# Schematic.net
KiCad netlist of a schematic drawn in Altium Designer
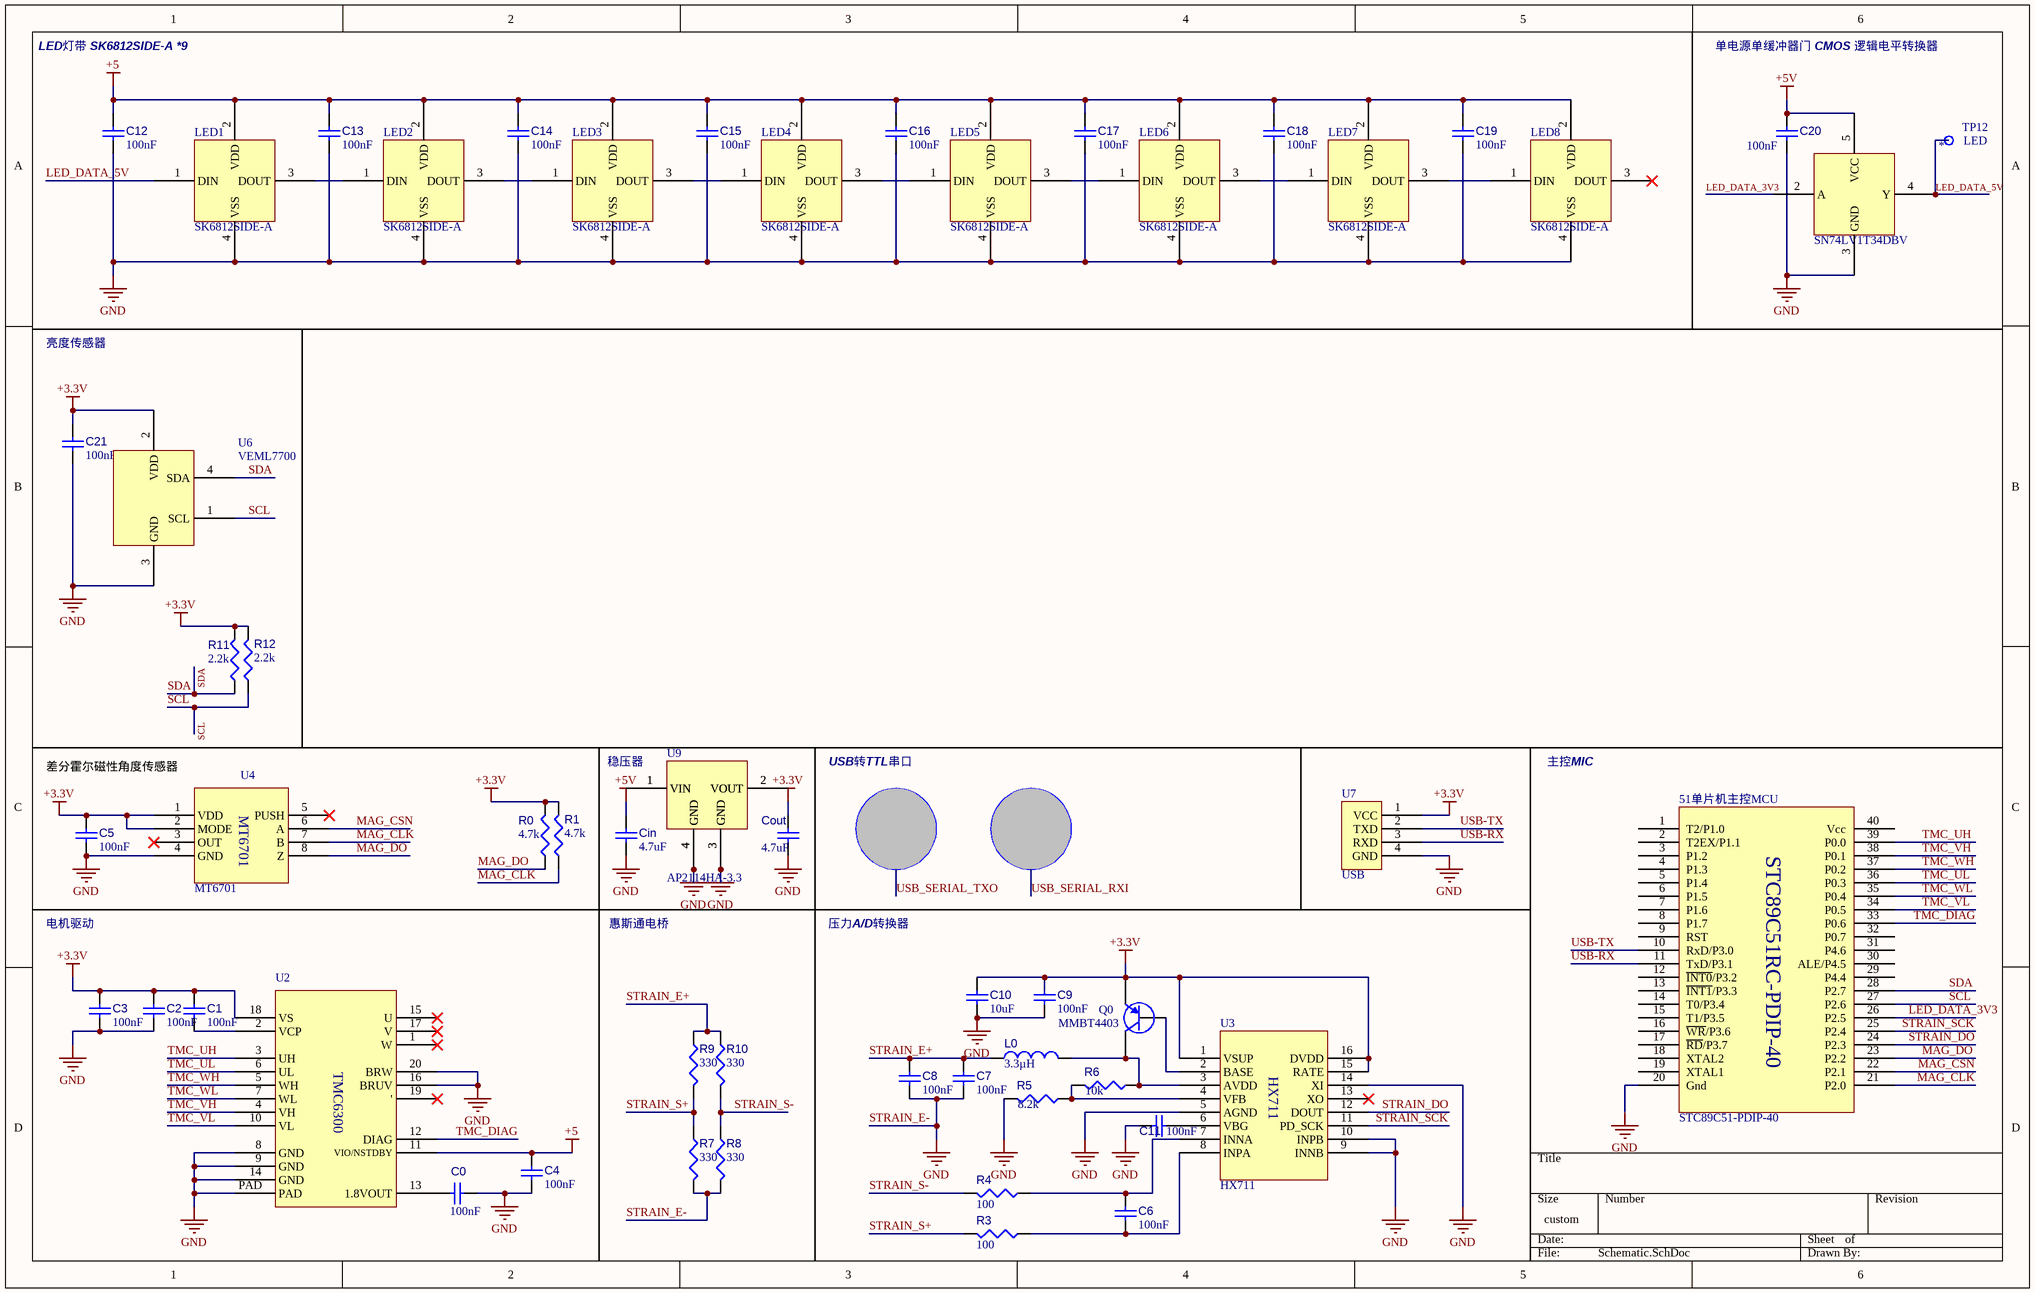
[diagram p0: Schematic.SchDoc]

(export (version "E")
  (design (tool "Eeschema 10.0.6"))
  (components
    (comp (ref "*")
      (value "SN74LV1T34DBV")
      (footprint "封装.SN74LV1T34DBVR")
      (description "电流放大器")
      (libsource (lib "DigiPCBA Workspace") (part "SN74LV1T34DBV"))
    )
    (comp (ref "51单片机主控MCU")
      (value "STC89C51-PDIP-40")
      (footprint "封装.STC89C51-PDIP-40")
      (description "主控MCU")
      (libsource (lib "DigiPCBA Workspace") (part "STC89C51-PDIP-40"))
    )
    (comp (ref "C0")
      (value "100nF")
      (footprint "CAPC1005X56X25LL10T15")
      (description "Chip Capacitor, 0.1 uF, +/- 5%, 16 V, 0402 (1005 Metric)")
      (fields (field (name "TOLERANCE") "5%") (field (name "Comment") "Capacitor 0.1 uF +/- 5% 16 V 0402"))
      (libsource (lib "IC") (part "CAP-NP-2"))
    )
    (comp (ref "C1")
      (value "100nF")
      (footprint "CAPC1005X56X25LL10T15")
      (description "Chip Capacitor, 0.1 uF, +/- 5%, 16 V, 0402 (1005 Metric)")
      (fields (field (name "TOLERANCE") "5%") (field (name "Comment") "Capacitor 0.1 uF +/- 5% 16 V 0402"))
      (libsource (lib "IC") (part "CAP-NP-2"))
    )
    (comp (ref "C2")
      (value "100nF")
      (footprint "CAPC1005X56X25LL10T15")
      (description "Chip Capacitor, 0.1 uF, +/- 5%, 16 V, 0402 (1005 Metric)")
      (fields (field (name "TOLERANCE") "5%") (field (name "Comment") "Capacitor 0.1 uF +/- 5% 16 V 0402"))
      (libsource (lib "IC") (part "CAP-NP-2"))
    )
    (comp (ref "C3")
      (value "100nF")
      (footprint "CAPC1005X56X25LL10T15")
      (description "Chip Capacitor, 0.1 uF, +/- 5%, 16 V, 0402 (1005 Metric)")
      (fields (field (name "TOLERANCE") "5%") (field (name "Comment") "Capacitor 0.1 uF +/- 5% 16 V 0402"))
      (libsource (lib "IC") (part "CAP-NP-2"))
    )
    (comp (ref "C4")
      (value "100nF")
      (footprint "CAPC1005X56X25LL10T15")
      (description "Chip Capacitor, 0.1 uF, +/- 5%, 16 V, 0402 (1005 Metric)")
      (fields (field (name "TOLERANCE") "5%") (field (name "Comment") "Capacitor 0.1 uF +/- 5% 16 V 0402"))
      (libsource (lib "IC") (part "CAP-NP-2"))
    )
    (comp (ref "C5")
      (value "100nF")
      (footprint "CAPC1005X56X25LL10T15")
      (description "Chip Capacitor, 0.1 uF, +/- 5%, 16 V, 0402 (1005 Metric)")
      (fields (field (name "TOLERANCE") "5%") (field (name "Comment") "Capacitor 0.1 uF +/- 5% 16 V 0402"))
      (libsource (lib "IC") (part "CAP-NP-2"))
    )
    (comp (ref "C6")
      (value "100nF")
      (footprint "CAPC1005X56X25LL10T15")
      (description "Chip Capacitor, 0.1 uF, +/- 5%, 16 V, 0402 (1005 Metric)")
      (fields (field (name "TOLERANCE") "5%") (field (name "Comment") "Capacitor 0.1 uF +/- 5% 16 V 0402"))
      (libsource (lib "IC") (part "CAP-NP-2"))
    )
    (comp (ref "C7")
      (value "100nF")
      (footprint "CAPC1005X56X25LL10T15")
      (description "Chip Capacitor, 0.1 uF, +/- 5%, 16 V, 0402 (1005 Metric)")
      (fields (field (name "TOLERANCE") "5%") (field (name "Comment") "Capacitor 0.1 uF +/- 5% 16 V 0402"))
      (libsource (lib "IC") (part "CAP-NP-2"))
    )
    (comp (ref "C8")
      (value "100nF")
      (footprint "CAPC1005X56X25LL10T15")
      (description "Chip Capacitor, 0.1 uF, +/- 5%, 16 V, 0402 (1005 Metric)")
      (fields (field (name "TOLERANCE") "5%") (field (name "Comment") "Capacitor 0.1 uF +/- 5% 16 V 0402"))
      (libsource (lib "IC") (part "CAP-NP-2"))
    )
    (comp (ref "C9")
      (value "100nF")
      (footprint "CAPC1005X56X25LL10T15")
      (description "Chip Capacitor, 0.1 uF, +/- 5%, 16 V, 0402 (1005 Metric)")
      (fields (field (name "TOLERANCE") "5%") (field (name "Comment") "Capacitor 0.1 uF +/- 5% 16 V 0402"))
      (libsource (lib "IC") (part "CAP-NP-2"))
    )
    (comp (ref "C10")
      (value "10uF")
      (footprint "CAPC1005X56X25LL10T15")
      (description "Chip Capacitor, 0.1 uF, +/- 5%, 16 V, 0402 (1005 Metric)")
      (fields (field (name "TOLERANCE") "5%") (field (name "Comment") "Capacitor 0.1 uF +/- 5% 16 V 0402"))
      (libsource (lib "IC") (part "CAP-NP-2"))
    )
    (comp (ref "C11")
      (value "100nF")
      (footprint "CAPC1005X56X25LL10T15")
      (description "Chip Capacitor, 0.1 uF, +/- 5%, 16 V, 0402 (1005 Metric)")
      (fields (field (name "TOLERANCE") "5%") (field (name "Comment") "Capacitor 0.1 uF +/- 5% 16 V 0402"))
      (libsource (lib "IC") (part "CAP-NP-2"))
    )
    (comp (ref "C12")
      (value "100nF")
      (footprint "CAPC1005X56X25LL10T15")
      (description "Chip Capacitor, 0.1 uF, +/- 5%, 16 V, 0402 (1005 Metric)")
      (fields (field (name "TOLERANCE") "5%") (field (name "Comment") "Capacitor 0.1 uF +/- 5% 16 V 0402"))
      (libsource (lib "IC") (part "CAP-NP-2"))
    )
    (comp (ref "C13")
      (value "100nF")
      (footprint "CAPC1005X56X25LL10T15")
      (description "Chip Capacitor, 0.1 uF, +/- 5%, 16 V, 0402 (1005 Metric)")
      (fields (field (name "TOLERANCE") "5%") (field (name "Comment") "Capacitor 0.1 uF +/- 5% 16 V 0402"))
      (libsource (lib "IC") (part "CAP-NP-2"))
    )
    (comp (ref "C14")
      (value "100nF")
      (footprint "CAPC1005X56X25LL10T15")
      (description "Chip Capacitor, 0.1 uF, +/- 5%, 16 V, 0402 (1005 Metric)")
      (fields (field (name "TOLERANCE") "5%") (field (name "Comment") "Capacitor 0.1 uF +/- 5% 16 V 0402"))
      (libsource (lib "IC") (part "CAP-NP-2"))
    )
    (comp (ref "C15")
      (value "100nF")
      (footprint "CAPC1005X56X25LL10T15")
      (description "Chip Capacitor, 0.1 uF, +/- 5%, 16 V, 0402 (1005 Metric)")
      (fields (field (name "TOLERANCE") "5%") (field (name "Comment") "Capacitor 0.1 uF +/- 5% 16 V 0402"))
      (libsource (lib "IC") (part "CAP-NP-2"))
    )
    (comp (ref "C16")
      (value "100nF")
      (footprint "CAPC1005X56X25LL10T15")
      (description "Chip Capacitor, 0.1 uF, +/- 5%, 16 V, 0402 (1005 Metric)")
      (fields (field (name "TOLERANCE") "5%") (field (name "Comment") "Capacitor 0.1 uF +/- 5% 16 V 0402"))
      (libsource (lib "IC") (part "CAP-NP-2"))
    )
    (comp (ref "C17")
      (value "100nF")
      (footprint "CAPC1005X56X25LL10T15")
      (description "Chip Capacitor, 0.1 uF, +/- 5%, 16 V, 0402 (1005 Metric)")
      (fields (field (name "TOLERANCE") "5%") (field (name "Comment") "Capacitor 0.1 uF +/- 5% 16 V 0402"))
      (libsource (lib "IC") (part "CAP-NP-2"))
    )
    (comp (ref "C18")
      (value "100nF")
      (footprint "CAPC1005X56X25LL10T15")
      (description "Chip Capacitor, 0.1 uF, +/- 5%, 16 V, 0402 (1005 Metric)")
      (fields (field (name "TOLERANCE") "5%") (field (name "Comment") "Capacitor 0.1 uF +/- 5% 16 V 0402"))
      (libsource (lib "IC") (part "CAP-NP-2"))
    )
    (comp (ref "C19")
      (value "100nF")
      (footprint "CAPC1005X56X25LL10T15")
      (description "Chip Capacitor, 0.1 uF, +/- 5%, 16 V, 0402 (1005 Metric)")
      (fields (field (name "TOLERANCE") "5%") (field (name "Comment") "Capacitor 0.1 uF +/- 5% 16 V 0402"))
      (libsource (lib "IC") (part "CAP-NP-2"))
    )
    (comp (ref "C20")
      (value "100nF")
      (footprint "CAPC1005X56X25LL10T15")
      (description "Chip Capacitor, 0.1 uF, +/- 5%, 16 V, 0402 (1005 Metric)")
      (fields (field (name "TOLERANCE") "5%") (field (name "Comment") "Capacitor 0.1 uF +/- 5% 16 V 0402"))
      (libsource (lib "IC") (part "CAP-NP-2"))
    )
    (comp (ref "C21")
      (value "100nF")
      (footprint "CAPC1005X56X25LL10T15")
      (description "Chip Capacitor, 0.1 uF, +/- 5%, 16 V, 0402 (1005 Metric)")
      (fields (field (name "TOLERANCE") "5%") (field (name "Comment") "Capacitor 0.1 uF +/- 5% 16 V 0402"))
      (libsource (lib "IC") (part "CAP-NP-2"))
    )
    (comp (ref "Cin")
      (value "4.7uF")
      (footprint "CAPC1005X56X25LL10T15")
      (description "Chip Capacitor, 0.1 uF, +/- 5%, 16 V, 0402 (1005 Metric)")
      (fields (field (name "TOLERANCE") "5%") (field (name "Comment") "Capacitor 0.1 uF +/- 5% 16 V 0402"))
      (libsource (lib "IC") (part "CAP-NP-2"))
    )
    (comp (ref "Cout")
      (value "4.7uF")
      (footprint "CAPC1005X56X25LL10T15")
      (description "Chip Capacitor, 0.1 uF, +/- 5%, 16 V, 0402 (1005 Metric)")
      (fields (field (name "TOLERANCE") "5%") (field (name "Comment") "Capacitor 0.1 uF +/- 5% 16 V 0402"))
      (libsource (lib "IC") (part "CAP-NP-2"))
    )
    (comp (ref "L0")
      (value "3.3µH")
      (footprint "INDC2520X120X60NL20T20")
      (description "Chip Inductor, 1 uH, +/- 20%, 1 MHz, -55 to 125 degC, 1008 (2520 Metric), RoHS, Tape and Reel")
      (fields (field (name "TOLERANCE") "20%") (field (name "MANUFACTURER") "Murata"))
      (libsource (lib "DigiPCBA Workspace") (part "IND-2"))
    )
    (comp (ref "LED1") (value "SK6812SIDE-A") (libsource (lib "DigiPCBA Workspace") (part "SK6812SIDE-A")))
    (comp (ref "LED2") (value "SK6812SIDE-A") (libsource (lib "DigiPCBA Workspace") (part "SK6812SIDE-A")))
    (comp (ref "LED3") (value "SK6812SIDE-A") (libsource (lib "DigiPCBA Workspace") (part "SK6812SIDE-A")))
    (comp (ref "LED4") (value "SK6812SIDE-A") (libsource (lib "DigiPCBA Workspace") (part "SK6812SIDE-A")))
    (comp (ref "LED5") (value "SK6812SIDE-A") (libsource (lib "DigiPCBA Workspace") (part "SK6812SIDE-A")))
    (comp (ref "LED6") (value "SK6812SIDE-A") (libsource (lib "DigiPCBA Workspace") (part "SK6812SIDE-A")))
    (comp (ref "LED7") (value "SK6812SIDE-A") (libsource (lib "DigiPCBA Workspace") (part "SK6812SIDE-A")))
    (comp (ref "LED8") (value "SK6812SIDE-A") (libsource (lib "DigiPCBA Workspace") (part "SK6812SIDE-A")))
    (comp (ref "Q0")
      (value "MMBT4403")
      (footprint "UNIC-TO-92-3")
      (description "Low Voltage High Current Small Signal PNP Transistor, 20 V, 700 mA, 3-Pin TO-92, RoHS")
      (fields (field (name "MANUFACTURER") "Unisonic"))
      (libsource (lib "DigiPCBA Workspace") (part "BJT-PNP-EBC-3"))
    )
    (comp (ref "R0")
      (value "4.7k")
      (footprint "RESC0402(1005)_L")
      (description "4K7 0.063W 1% 0402 (1005 Metric)  SMD")
      (fields (field (name "TOLERANCE") "1%") (field (name "POWER") "63mW"))
      (libsource (lib "DigiPCBA Workspace") (part "4D7KR2F"))
    )
    (comp (ref "R1")
      (value "4.7k")
      (footprint "RESC0402(1005)_L")
      (description "4K7 0.063W 1% 0402 (1005 Metric)  SMD")
      (fields (field (name "TOLERANCE") "1%") (field (name "POWER") "63mW"))
      (libsource (lib "DigiPCBA Workspace") (part "4D7KR2F"))
    )
    (comp (ref "R3")
      (value "100")
      (footprint "RESC0402(1005)_L")
      (description "4K7 0.063W 1% 0402 (1005 Metric)  SMD")
      (fields (field (name "TOLERANCE") "1%") (field (name "POWER") "63mW"))
      (libsource (lib "DigiPCBA Workspace") (part "4D7KR2F"))
    )
    (comp (ref "R4")
      (value "100")
      (footprint "RESC0402(1005)_L")
      (description "4K7 0.063W 1% 0402 (1005 Metric)  SMD")
      (fields (field (name "TOLERANCE") "1%") (field (name "POWER") "63mW"))
      (libsource (lib "DigiPCBA Workspace") (part "4D7KR2F"))
    )
    (comp (ref "R5")
      (value "8.2k")
      (footprint "RESC0402(1005)_L")
      (description "4K7 0.063W 1% 0402 (1005 Metric)  SMD")
      (fields (field (name "TOLERANCE") "1%") (field (name "POWER") "63mW"))
      (libsource (lib "DigiPCBA Workspace") (part "4D7KR2F"))
    )
    (comp (ref "R6")
      (value "10k")
      (footprint "RESC0402(1005)_L")
      (description "4K7 0.063W 1% 0402 (1005 Metric)  SMD")
      (fields (field (name "TOLERANCE") "1%") (field (name "POWER") "63mW"))
      (libsource (lib "DigiPCBA Workspace") (part "4D7KR2F"))
    )
    (comp (ref "R7")
      (value "330")
      (footprint "RESC0402(1005)_L")
      (description "4K7 0.063W 1% 0402 (1005 Metric)  SMD")
      (fields (field (name "TOLERANCE") "1%") (field (name "POWER") "63mW"))
      (libsource (lib "DigiPCBA Workspace") (part "4D7KR2F"))
    )
    (comp (ref "R8")
      (value "330")
      (footprint "RESC0402(1005)_L")
      (description "4K7 0.063W 1% 0402 (1005 Metric)  SMD")
      (fields (field (name "TOLERANCE") "1%") (field (name "POWER") "63mW"))
      (libsource (lib "DigiPCBA Workspace") (part "4D7KR2F"))
    )
    (comp (ref "R9")
      (value "330")
      (footprint "RESC0402(1005)_L")
      (description "4K7 0.063W 1% 0402 (1005 Metric)  SMD")
      (fields (field (name "TOLERANCE") "1%") (field (name "POWER") "63mW"))
      (libsource (lib "DigiPCBA Workspace") (part "4D7KR2F"))
    )
    (comp (ref "R10")
      (value "330")
      (footprint "RESC0402(1005)_L")
      (description "4K7 0.063W 1% 0402 (1005 Metric)  SMD")
      (fields (field (name "TOLERANCE") "1%") (field (name "POWER") "63mW"))
      (libsource (lib "DigiPCBA Workspace") (part "4D7KR2F"))
    )
    (comp (ref "R11")
      (value "2.2k")
      (footprint "RESC0402(1005)_L")
      (description "4K7 0.063W 1% 0402 (1005 Metric)  SMD")
      (fields (field (name "TOLERANCE") "1%") (field (name "POWER") "63mW"))
      (libsource (lib "DigiPCBA Workspace") (part "4D7KR2F"))
    )
    (comp (ref "R12")
      (value "2.2k")
      (footprint "RESC0402(1005)_L")
      (description "4K7 0.063W 1% 0402 (1005 Metric)  SMD")
      (fields (field (name "TOLERANCE") "1%") (field (name "POWER") "63mW"))
      (libsource (lib "DigiPCBA Workspace") (part "4D7KR2F"))
    )
    (comp (ref "TMC1") (value "U2") (libsource (lib "DigiPCBA Workspace") (part "TMC6300")))
    (comp (ref "U3")
      (value "HX711")
      (footprint "封装.HX711")
      (description "压力模数转换器")
      (libsource (lib "DigiPCBA Workspace") (part "HX711"))
    )
    (comp (ref "U4") (value "MT6701") (libsource (lib "DigiPCBA Workspace") (part "MT6701")))
    (comp (ref "U6")
      (value "VEML7700")
      (footprint "封装.VEML7700")
      (description "感光想读传感器")
      (libsource (lib "DigiPCBA Workspace") (part "VEML7700"))
    )
    (comp (ref "U7") (value "USB") (libsource (lib "DigiPCBA Workspace") (part "USB")))
    (comp (ref "U9")
      (value "AP2114HA-3.3")
      (footprint "封装.AP2114HA-3.3TRG1")
      (description "电压控制器")
      (libsource (lib "DigiPCBA Workspace") (part "AP2114HA-3.3"))
    )
  )
  (nets
    (net (code "1") (name "+3.3V") (class "Default")
      (node (ref "C1") (pin "1") (pinfunction "1_1") (pintype "passive"))
      (node (ref "C10") (pin "1") (pinfunction "1_1") (pintype "passive"))
      (node (ref "C2") (pin "1") (pinfunction "1_1") (pintype "passive"))
      (node (ref "C21") (pin "1") (pinfunction "1_1") (pintype "passive"))
      (node (ref "C3") (pin "1") (pinfunction "1_1") (pintype "passive"))
      (node (ref "C5") (pin "1") (pinfunction "1_1") (pintype "passive"))
      (node (ref "C9") (pin "1") (pinfunction "1_1") (pintype "passive"))
      (node (ref "Cout") (pin "1") (pinfunction "1_1") (pintype "passive"))
      (node (ref "Q0") (pin "1") (pinfunction "E_1") (pintype "passive"))
      (node (ref "R0") (pin "2") (pinfunction "2_2") (pintype "passive"))
      (node (ref "R1") (pin "2") (pinfunction "2_2") (pintype "passive"))
      (node (ref "R11") (pin "2") (pinfunction "2_2") (pintype "passive"))
      (node (ref "R12") (pin "2") (pinfunction "2_2") (pintype "passive"))
      (node (ref "TMC1") (pin "18") (pinfunction "VS_18") (pintype "open_collector"))
      (node (ref "U3") (pin "1") (pinfunction "VSUP_1") (pintype "open_collector"))
      (node (ref "U3") (pin "15") (pinfunction "RATE_15") (pintype "open_collector"))
      (node (ref "U3") (pin "16") (pinfunction "DVDD_16") (pintype "open_collector"))
      (node (ref "U4") (pin "1") (pinfunction "VDD_1") (pintype "open_collector"))
      (node (ref "U4") (pin "2") (pinfunction "MODE_2") (pintype "open_collector"))
      (node (ref "U6") (pin "2") (pinfunction "VDD_2") (pintype "open_collector"))
      (node (ref "U7") (pin "1") (pinfunction "VCC_1") (pintype "open_collector"))
    )
    (net (code "2") (name "+5") (class "Default")
      (node (ref "C12") (pin "1") (pinfunction "1_1") (pintype "passive"))
      (node (ref "C13") (pin "1") (pinfunction "1_1") (pintype "passive"))
      (node (ref "C14") (pin "1") (pinfunction "1_1") (pintype "passive"))
      (node (ref "C15") (pin "1") (pinfunction "1_1") (pintype "passive"))
      (node (ref "C16") (pin "1") (pinfunction "1_1") (pintype "passive"))
      (node (ref "C17") (pin "1") (pinfunction "1_1") (pintype "passive"))
      (node (ref "C18") (pin "1") (pinfunction "1_1") (pintype "passive"))
      (node (ref "C19") (pin "1") (pinfunction "1_1") (pintype "passive"))
      (node (ref "C4") (pin "1") (pinfunction "1_1") (pintype "passive"))
      (node (ref "LED1") (pin "2") (pinfunction "VDD_2") (pintype "open_collector"))
      (node (ref "LED2") (pin "2") (pinfunction "VDD_2") (pintype "open_collector"))
      (node (ref "LED3") (pin "2") (pinfunction "VDD_2") (pintype "open_collector"))
      (node (ref "LED4") (pin "2") (pinfunction "VDD_2") (pintype "open_collector"))
      (node (ref "LED5") (pin "2") (pinfunction "VDD_2") (pintype "open_collector"))
      (node (ref "LED6") (pin "2") (pinfunction "VDD_2") (pintype "open_collector"))
      (node (ref "LED7") (pin "2") (pinfunction "VDD_2") (pintype "open_collector"))
      (node (ref "LED8") (pin "2") (pinfunction "VDD_2") (pintype "open_collector"))
      (node (ref "TMC1") (pin "11") (pinfunction "VIO/NSTDBY_11") (pintype "open_collector"))
    )
    (net (code "3") (name "+5V") (class "Default")
      (node (ref "*") (pin "5") (pinfunction "VCC_5") (pintype "open_collector"))
      (node (ref "C20") (pin "1") (pinfunction "1_1") (pintype "passive"))
      (node (ref "Cin") (pin "1") (pinfunction "1_1") (pintype "passive"))
    )
    (net (code "4") (name "/LED_DATA_3V3") (class "Default")
      (node (ref "*") (pin "2") (pinfunction "A_2") (pintype "open_collector"))
      (node (ref "51单片机主控MCU") (pin "26") (pinfunction "P2.5_26") (pintype "open_collector"))
    )
    (net (code "5") (name "/LED_DATA_5V") (class "Default")
      (node (ref "*") (pin "4") (pinfunction "Y_4") (pintype "open_collector"))
      (node (ref "LED1") (pin "1") (pinfunction "DIN_1") (pintype "open_collector"))
    )
    (net (code "6") (name "/MAG_CLK") (class "Default")
      (node (ref "51单片机主控MCU") (pin "21") (pinfunction "P2.0_21") (pintype "open_collector"))
      (node (ref "R1") (pin "1") (pinfunction "1_1") (pintype "passive"))
      (node (ref "U4") (pin "7") (pinfunction "B_7") (pintype "open_collector"))
    )
    (net (code "7") (name "/MAG_CSN") (class "Default")
      (node (ref "51单片机主控MCU") (pin "22") (pinfunction "P2.1_22") (pintype "open_collector"))
      (node (ref "U4") (pin "6") (pinfunction "A_6") (pintype "open_collector"))
    )
    (net (code "8") (name "/MAG_DO") (class "Default")
      (node (ref "51单片机主控MCU") (pin "23") (pinfunction "P2.2_23") (pintype "open_collector"))
      (node (ref "R0") (pin "1") (pinfunction "1_1") (pintype "passive"))
      (node (ref "U4") (pin "8") (pinfunction "Z_8") (pintype "open_collector"))
    )
    (net (code "9") (name "/SCL") (class "Default")
      (node (ref "51单片机主控MCU") (pin "27") (pinfunction "P2.6_27") (pintype "open_collector"))
      (node (ref "R12") (pin "1") (pinfunction "1_1") (pintype "passive"))
      (node (ref "U6") (pin "1") (pinfunction "SCL_1") (pintype "open_collector"))
    )
    (net (code "10") (name "/SDA") (class "Default")
      (node (ref "51单片机主控MCU") (pin "28") (pinfunction "P2.7_28") (pintype "open_collector"))
      (node (ref "R11") (pin "1") (pinfunction "1_1") (pintype "passive"))
      (node (ref "U6") (pin "4") (pinfunction "SDA_4") (pintype "open_collector"))
    )
    (net (code "11") (name "/STRAIN_DO") (class "Default")
      (node (ref "51单片机主控MCU") (pin "24") (pinfunction "P2.3_24") (pintype "open_collector"))
      (node (ref "U3") (pin "12") (pinfunction "DOUT_12") (pintype "open_collector"))
    )
    (net (code "12") (name "/STRAIN_E+") (class "Default")
      (node (ref "C7") (pin "1") (pinfunction "1_1") (pintype "passive"))
      (node (ref "C8") (pin "1") (pinfunction "1_1") (pintype "passive"))
      (node (ref "L0") (pin "1") (pinfunction "1_1") (pintype "passive"))
      (node (ref "R10") (pin "1") (pinfunction "1_1") (pintype "passive"))
      (node (ref "R9") (pin "1") (pinfunction "1_1") (pintype "passive"))
    )
    (net (code "13") (name "/STRAIN_S+") (class "Default")
      (node (ref "R3") (pin "2") (pinfunction "2_2") (pintype "passive"))
      (node (ref "R7") (pin "1") (pinfunction "1_1") (pintype "passive"))
      (node (ref "R9") (pin "2") (pinfunction "2_2") (pintype "passive"))
    )
    (net (code "14") (name "/STRAIN_S-") (class "Default")
      (node (ref "R10") (pin "2") (pinfunction "2_2") (pintype "passive"))
      (node (ref "R4") (pin "2") (pinfunction "2_2") (pintype "passive"))
      (node (ref "R8") (pin "1") (pinfunction "1_1") (pintype "passive"))
    )
    (net (code "15") (name "/STRAIN_SCK") (class "Default")
      (node (ref "51单片机主控MCU") (pin "25") (pinfunction "P2.4_25") (pintype "open_collector"))
      (node (ref "U3") (pin "11") (pinfunction "PD_SCK_11") (pintype "open_collector"))
    )
    (net (code "16") (name "/TMC_DIAG") (class "Default")
      (node (ref "51单片机主控MCU") (pin "33") (pinfunction "P0.6_33") (pintype "open_collector"))
      (node (ref "TMC1") (pin "12") (pinfunction "DIAG_12") (pintype "open_collector"))
    )
    (net (code "17") (name "/TMC_UH") (class "Default")
      (node (ref "51单片机主控MCU") (pin "39") (pinfunction "P0.0_39") (pintype "open_collector"))
      (node (ref "TMC1") (pin "3") (pinfunction "UH_3") (pintype "open_collector"))
    )
    (net (code "18") (name "/TMC_UL") (class "Default")
      (node (ref "51单片机主控MCU") (pin "36") (pinfunction "P0.3_36") (pintype "open_collector"))
      (node (ref "TMC1") (pin "6") (pinfunction "UL_6") (pintype "open_collector"))
    )
    (net (code "19") (name "/TMC_VH") (class "Default")
      (node (ref "51单片机主控MCU") (pin "38") (pinfunction "P0.1_38") (pintype "open_collector"))
      (node (ref "TMC1") (pin "4") (pinfunction "VH_4") (pintype "open_collector"))
    )
    (net (code "20") (name "/TMC_VL") (class "Default")
      (node (ref "51单片机主控MCU") (pin "34") (pinfunction "P0.5_34") (pintype "open_collector"))
      (node (ref "TMC1") (pin "10") (pinfunction "VL_10") (pintype "open_collector"))
    )
    (net (code "21") (name "/TMC_WH") (class "Default")
      (node (ref "51单片机主控MCU") (pin "37") (pinfunction "P0.2_37") (pintype "open_collector"))
      (node (ref "TMC1") (pin "5") (pinfunction "WH_5") (pintype "open_collector"))
    )
    (net (code "22") (name "/TMC_WL") (class "Default")
      (node (ref "51单片机主控MCU") (pin "35") (pinfunction "P0.4_35") (pintype "open_collector"))
      (node (ref "TMC1") (pin "7") (pinfunction "WL_7") (pintype "open_collector"))
    )
    (net (code "23") (name "/USB-RX") (class "Default")
      (node (ref "51单片机主控MCU") (pin "11") (pinfunction "TxD/P3.1_11") (pintype "open_collector"))
      (node (ref "U7") (pin "3") (pinfunction "RXD_3") (pintype "open_collector"))
    )
    (net (code "24") (name "/USB-TX") (class "Default")
      (node (ref "51单片机主控MCU") (pin "10") (pinfunction "RxD/P3.0_10") (pintype "open_collector"))
      (node (ref "U7") (pin "2") (pinfunction "TXD_2") (pintype "open_collector"))
    )
    (net (code "27") (name "GND") (class "Default")
      (node (ref "*") (pin "3") (pinfunction "GND_3") (pintype "open_collector"))
      (node (ref "51单片机主控MCU") (pin "20") (pinfunction "Gnd_20") (pintype "open_collector"))
      (node (ref "C0") (pin "1") (pinfunction "1_1") (pintype "passive"))
      (node (ref "C10") (pin "2") (pinfunction "2_2") (pintype "passive"))
      (node (ref "C11") (pin "1") (pinfunction "1_1") (pintype "passive"))
      (node (ref "C12") (pin "2") (pinfunction "2_2") (pintype "passive"))
      (node (ref "C13") (pin "2") (pinfunction "2_2") (pintype "passive"))
      (node (ref "C14") (pin "2") (pinfunction "2_2") (pintype "passive"))
      (node (ref "C15") (pin "2") (pinfunction "2_2") (pintype "passive"))
      (node (ref "C16") (pin "2") (pinfunction "2_2") (pintype "passive"))
      (node (ref "C17") (pin "2") (pinfunction "2_2") (pintype "passive"))
      (node (ref "C18") (pin "2") (pinfunction "2_2") (pintype "passive"))
      (node (ref "C19") (pin "2") (pinfunction "2_2") (pintype "passive"))
      (node (ref "C2") (pin "2") (pinfunction "2_2") (pintype "passive"))
      (node (ref "C20") (pin "2") (pinfunction "2_2") (pintype "passive"))
      (node (ref "C21") (pin "2") (pinfunction "2_2") (pintype "passive"))
      (node (ref "C3") (pin "2") (pinfunction "2_2") (pintype "passive"))
      (node (ref "C4") (pin "2") (pinfunction "2_2") (pintype "passive"))
      (node (ref "C5") (pin "2") (pinfunction "2_2") (pintype "passive"))
      (node (ref "C7") (pin "2") (pinfunction "2_2") (pintype "passive"))
      (node (ref "C8") (pin "2") (pinfunction "2_2") (pintype "passive"))
      (node (ref "C9") (pin "2") (pinfunction "2_2") (pintype "passive"))
      (node (ref "Cin") (pin "2") (pinfunction "2_2") (pintype "passive"))
      (node (ref "Cout") (pin "2") (pinfunction "2_2") (pintype "passive"))
      (node (ref "LED1") (pin "4") (pinfunction "VSS_4") (pintype "open_collector"))
      (node (ref "LED2") (pin "4") (pinfunction "VSS_4") (pintype "open_collector"))
      (node (ref "LED3") (pin "4") (pinfunction "VSS_4") (pintype "open_collector"))
      (node (ref "LED4") (pin "4") (pinfunction "VSS_4") (pintype "open_collector"))
      (node (ref "LED5") (pin "4") (pinfunction "VSS_4") (pintype "open_collector"))
      (node (ref "LED6") (pin "4") (pinfunction "VSS_4") (pintype "open_collector"))
      (node (ref "LED7") (pin "4") (pinfunction "VSS_4") (pintype "open_collector"))
      (node (ref "LED8") (pin "4") (pinfunction "VSS_4") (pintype "open_collector"))
      (node (ref "R5") (pin "2") (pinfunction "2_2") (pintype "passive"))
      (node (ref "R7") (pin "2") (pinfunction "2_2") (pintype "passive"))
      (node (ref "R8") (pin "2") (pinfunction "2_2") (pintype "passive"))
      (node (ref "TMC1") (pin "14") (pinfunction "GND_14") (pintype "open_collector"))
      (node (ref "TMC1") (pin "16") (pinfunction "BRUV_16") (pintype "open_collector"))
      (node (ref "TMC1") (pin "20") (pinfunction "BRW_20") (pintype "open_collector"))
      (node (ref "TMC1") (pin "8") (pinfunction "GND_8") (pintype "open_collector"))
      (node (ref "TMC1") (pin "9") (pinfunction "GND_9") (pintype "open_collector"))
      (node (ref "TMC1") (pin "PAD") (pinfunction "PAD_PAD") (pintype "open_collector"))
      (node (ref "U3") (pin "10") (pinfunction "INPB_10") (pintype "open_collector"))
      (node (ref "U3") (pin "14") (pinfunction "XI_14") (pintype "open_collector"))
      (node (ref "U3") (pin "5") (pinfunction "AGND_5") (pintype "open_collector"))
      (node (ref "U3") (pin "9") (pinfunction "INNB_9") (pintype "open_collector"))
      (node (ref "U4") (pin "4") (pinfunction "GND_4") (pintype "open_collector"))
      (node (ref "U6") (pin "3") (pinfunction "GND_3") (pintype "open_collector"))
      (node (ref "U7") (pin "4") (pinfunction "GND_4") (pintype "open_collector"))
      (node (ref "U9") (pin "3") (pinfunction "GND_3") (pintype "open_collector"))
      (node (ref "U9") (pin "4") (pinfunction "GND_4") (pintype "open_collector"))
    )
    (net (code "28") (name "Net-(LED1-DOUT)") (class "Default")
      (node (ref "LED1") (pin "3") (pinfunction "DOUT_3") (pintype "open_collector"))
      (node (ref "LED2") (pin "1") (pinfunction "DIN_1") (pintype "open_collector"))
    )
    (net (code "29") (name "Net-(LED2-DOUT)") (class "Default")
      (node (ref "LED2") (pin "3") (pinfunction "DOUT_3") (pintype "open_collector"))
      (node (ref "LED3") (pin "1") (pinfunction "DIN_1") (pintype "open_collector"))
    )
    (net (code "30") (name "Net-(LED3-DOUT)") (class "Default")
      (node (ref "LED3") (pin "3") (pinfunction "DOUT_3") (pintype "open_collector"))
      (node (ref "LED4") (pin "1") (pinfunction "DIN_1") (pintype "open_collector"))
    )
    (net (code "31") (name "Net-(LED4-DOUT)") (class "Default")
      (node (ref "LED4") (pin "3") (pinfunction "DOUT_3") (pintype "open_collector"))
      (node (ref "LED5") (pin "1") (pinfunction "DIN_1") (pintype "open_collector"))
    )
    (net (code "32") (name "Net-(LED5-DOUT)") (class "Default")
      (node (ref "LED5") (pin "3") (pinfunction "DOUT_3") (pintype "open_collector"))
      (node (ref "LED6") (pin "1") (pinfunction "DIN_1") (pintype "open_collector"))
    )
    (net (code "33") (name "Net-(LED6-DOUT)") (class "Default")
      (node (ref "LED6") (pin "3") (pinfunction "DOUT_3") (pintype "open_collector"))
      (node (ref "LED7") (pin "1") (pinfunction "DIN_1") (pintype "open_collector"))
    )
    (net (code "34") (name "Net-(LED7-DOUT)") (class "Default")
      (node (ref "LED7") (pin "3") (pinfunction "DOUT_3") (pintype "open_collector"))
      (node (ref "LED8") (pin "1") (pinfunction "DIN_1") (pintype "open_collector"))
    )
    (net (code "35") (name "Net-(Q0-B)") (class "Default")
      (node (ref "Q0") (pin "2") (pinfunction "B_2") (pintype "passive"))
      (node (ref "U3") (pin "2") (pinfunction "BASE_2") (pintype "open_collector"))
    )
    (net (code "36") (name "Net-(Q0-C)") (class "Default")
      (node (ref "L0") (pin "2") (pinfunction "2_2") (pintype "passive"))
      (node (ref "Q0") (pin "3") (pinfunction "C_3") (pintype "passive"))
      (node (ref "R6") (pin "1") (pinfunction "1_1") (pintype "passive"))
      (node (ref "U3") (pin "3") (pinfunction "AVDD_3") (pintype "open_collector"))
    )
    (net (code "37") (name "Net-(TMC1-1.8VOUT)") (class "Default")
      (node (ref "C0") (pin "2") (pinfunction "2_2") (pintype "passive"))
      (node (ref "TMC1") (pin "13") (pinfunction "1.8VOUT_13") (pintype "open_collector"))
    )
    (net (code "38") (name "Net-(TMC1-VCP)") (class "Default")
      (node (ref "C1") (pin "2") (pinfunction "2_2") (pintype "passive"))
      (node (ref "TMC1") (pin "2") (pinfunction "VCP_2") (pintype "open_collector"))
    )
    (net (code "39") (name "Net-(U3-INNA)") (class "Default")
      (node (ref "C6") (pin "1") (pinfunction "1_1") (pintype "passive"))
      (node (ref "R4") (pin "1") (pinfunction "1_1") (pintype "passive"))
      (node (ref "U3") (pin "7") (pinfunction "INNA_7") (pintype "open_collector"))
    )
    (net (code "40") (name "Net-(U3-INPA)") (class "Default")
      (node (ref "C6") (pin "2") (pinfunction "2_2") (pintype "passive"))
      (node (ref "R3") (pin "1") (pinfunction "1_1") (pintype "passive"))
      (node (ref "U3") (pin "8") (pinfunction "INPA_8") (pintype "open_collector"))
    )
    (net (code "41") (name "Net-(U3-VBG)") (class "Default")
      (node (ref "C11") (pin "2") (pinfunction "2_2") (pintype "passive"))
      (node (ref "U3") (pin "6") (pinfunction "VBG_6") (pintype "open_collector"))
    )
    (net (code "42") (name "Net-(U3-VFB)") (class "Default")
      (node (ref "R5") (pin "1") (pinfunction "1_1") (pintype "passive"))
      (node (ref "R6") (pin "2") (pinfunction "2_2") (pintype "passive"))
      (node (ref "U3") (pin "4") (pinfunction "VFB_4") (pintype "open_collector"))
    )
    (net (code "43") (name "Net-(U9-VIN)") (class "Default")
      (node (ref "U9") (pin "1") (pinfunction "VIN_1") (pintype "open_collector"))
    )
    (net (code "44") (name "Net-(U9-VOUT)") (class "Default")
      (node (ref "U9") (pin "2") (pinfunction "VOUT_2") (pintype "open_collector"))
    )
    (net (code "45") (name "unconnected-(51单片机主控MCU-ALE{slash}P4.5-Pad30)") (class "Default")
      (node (ref "51单片机主控MCU") (pin "30") (pinfunction "ALE/P4.5_30") (pintype "open_collector"))
    )
    (net (code "46") (name "unconnected-(51单片机主控MCU-P0.7-Pad32)") (class "Default")
      (node (ref "51单片机主控MCU") (pin "32") (pinfunction "P0.7_32") (pintype "open_collector"))
    )
    (net (code "47") (name "unconnected-(51单片机主控MCU-P1.2-Pad3)") (class "Default")
      (node (ref "51单片机主控MCU") (pin "3") (pinfunction "P1.2_3") (pintype "open_collector"))
    )
    (net (code "48") (name "unconnected-(51单片机主控MCU-P1.3-Pad4)") (class "Default")
      (node (ref "51单片机主控MCU") (pin "4") (pinfunction "P1.3_4") (pintype "open_collector"))
    )
    (net (code "49") (name "unconnected-(51单片机主控MCU-P1.4-Pad5)") (class "Default")
      (node (ref "51单片机主控MCU") (pin "5") (pinfunction "P1.4_5") (pintype "open_collector"))
    )
    (net (code "50") (name "unconnected-(51单片机主控MCU-P1.5-Pad6)") (class "Default")
      (node (ref "51单片机主控MCU") (pin "6") (pinfunction "P1.5_6") (pintype "open_collector"))
    )
    (net (code "51") (name "unconnected-(51单片机主控MCU-P1.6-Pad7)") (class "Default")
      (node (ref "51单片机主控MCU") (pin "7") (pinfunction "P1.6_7") (pintype "open_collector"))
    )
    (net (code "52") (name "unconnected-(51单片机主控MCU-P1.7-Pad8)") (class "Default")
      (node (ref "51单片机主控MCU") (pin "8") (pinfunction "P1.7_8") (pintype "open_collector"))
    )
    (net (code "53") (name "unconnected-(51单片机主控MCU-P4.4-Pad29)") (class "Default")
      (node (ref "51单片机主控MCU") (pin "29") (pinfunction "P4.4_29") (pintype "open_collector"))
    )
    (net (code "54") (name "unconnected-(51单片机主控MCU-P4.6-Pad31)") (class "Default")
      (node (ref "51单片机主控MCU") (pin "31") (pinfunction "P4.6_31") (pintype "open_collector"))
    )
    (net (code "55") (name "unconnected-(51单片机主控MCU-RST-Pad9)") (class "Default")
      (node (ref "51单片机主控MCU") (pin "9") (pinfunction "RST_9") (pintype "open_collector"))
    )
    (net (code "56") (name "unconnected-(51单片机主控MCU-T0{slash}P3.4-Pad14)") (class "Default")
      (node (ref "51单片机主控MCU") (pin "14") (pinfunction "T0/P3.4_14") (pintype "open_collector"))
    )
    (net (code "57") (name "unconnected-(51单片机主控MCU-T1{slash}P3.5-Pad15)") (class "Default")
      (node (ref "51单片机主控MCU") (pin "15") (pinfunction "T1/P3.5_15") (pintype "open_collector"))
    )
    (net (code "58") (name "unconnected-(51单片机主控MCU-T2EX{slash}P1.1-Pad2)") (class "Default")
      (node (ref "51单片机主控MCU") (pin "2") (pinfunction "T2EX/P1.1_2") (pintype "open_collector"))
    )
    (net (code "59") (name "unconnected-(51单片机主控MCU-T2{slash}P1.0-Pad1)") (class "Default")
      (node (ref "51单片机主控MCU") (pin "1") (pinfunction "T2/P1.0_1") (pintype "open_collector"))
    )
    (net (code "60") (name "unconnected-(51单片机主控MCU-Vcc-Pad40)") (class "Default")
      (node (ref "51单片机主控MCU") (pin "40") (pinfunction "Vcc_40") (pintype "open_collector"))
    )
    (net (code "61") (name "unconnected-(51单片机主控MCU-XTAL1-Pad19)") (class "Default")
      (node (ref "51单片机主控MCU") (pin "19") (pinfunction "XTAL1_19") (pintype "open_collector"))
    )
    (net (code "62") (name "unconnected-(51单片机主控MCU-XTAL2-Pad18)") (class "Default")
      (node (ref "51单片机主控MCU") (pin "18") (pinfunction "XTAL2_18") (pintype "open_collector"))
    )
    (net (code "63") (name "unconnected-(51单片机主控MCU-~{INT0}{slash}P3.2-Pad12)") (class "Default")
      (node (ref "51单片机主控MCU") (pin "12") (pinfunction "~{INT0}/P3.2_12") (pintype "open_collector"))
    )
    (net (code "64") (name "unconnected-(51单片机主控MCU-~{INT1}{slash}P3.3-Pad13)") (class "Default")
      (node (ref "51单片机主控MCU") (pin "13") (pinfunction "~{INT1}/P3.3_13") (pintype "open_collector"))
    )
    (net (code "65") (name "unconnected-(51单片机主控MCU-~{RD}{slash}P3.7-Pad17)") (class "Default")
      (node (ref "51单片机主控MCU") (pin "17") (pinfunction "~{RD}/P3.7_17") (pintype "open_collector"))
    )
    (net (code "66") (name "unconnected-(51单片机主控MCU-~{WR}{slash}P3.6-Pad16)") (class "Default")
      (node (ref "51单片机主控MCU") (pin "16") (pinfunction "~{WR}/P3.6_16") (pintype "open_collector"))
    )
    (net (code "67") (name "unconnected-(LED8-DOUT-Pad3)") (class "Default")
      (node (ref "LED8") (pin "3") (pinfunction "DOUT_3") (pintype "open_collector+no_connect"))
    )
    (net (code "68") (name "unconnected-(TMC1-'-Pad19)") (class "Default")
      (node (ref "TMC1") (pin "19") (pinfunction "'_19") (pintype "open_collector+no_connect"))
    )
    (net (code "69") (name "unconnected-(TMC1-U-Pad15)") (class "Default")
      (node (ref "TMC1") (pin "15") (pinfunction "U_15") (pintype "open_collector+no_connect"))
    )
    (net (code "70") (name "unconnected-(TMC1-V-Pad17)") (class "Default")
      (node (ref "TMC1") (pin "17") (pinfunction "V_17") (pintype "open_collector+no_connect"))
    )
    (net (code "71") (name "unconnected-(TMC1-W-Pad1)") (class "Default")
      (node (ref "TMC1") (pin "1") (pinfunction "W_1") (pintype "open_collector+no_connect"))
    )
    (net (code "72") (name "unconnected-(U3-XO-Pad13)") (class "Default")
      (node (ref "U3") (pin "13") (pinfunction "XO_13") (pintype "open_collector+no_connect"))
    )
    (net (code "73") (name "unconnected-(U4-OUT-Pad3)") (class "Default")
      (node (ref "U4") (pin "3") (pinfunction "OUT_3") (pintype "open_collector+no_connect"))
    )
    (net (code "74") (name "unconnected-(U4-PUSH-Pad5)") (class "Default")
      (node (ref "U4") (pin "5") (pinfunction "PUSH_5") (pintype "open_collector+no_connect"))
    )
  )
)
